# CTENLEDDRVR.net
KiCad netlist of a schematic drawn in Altium Designer
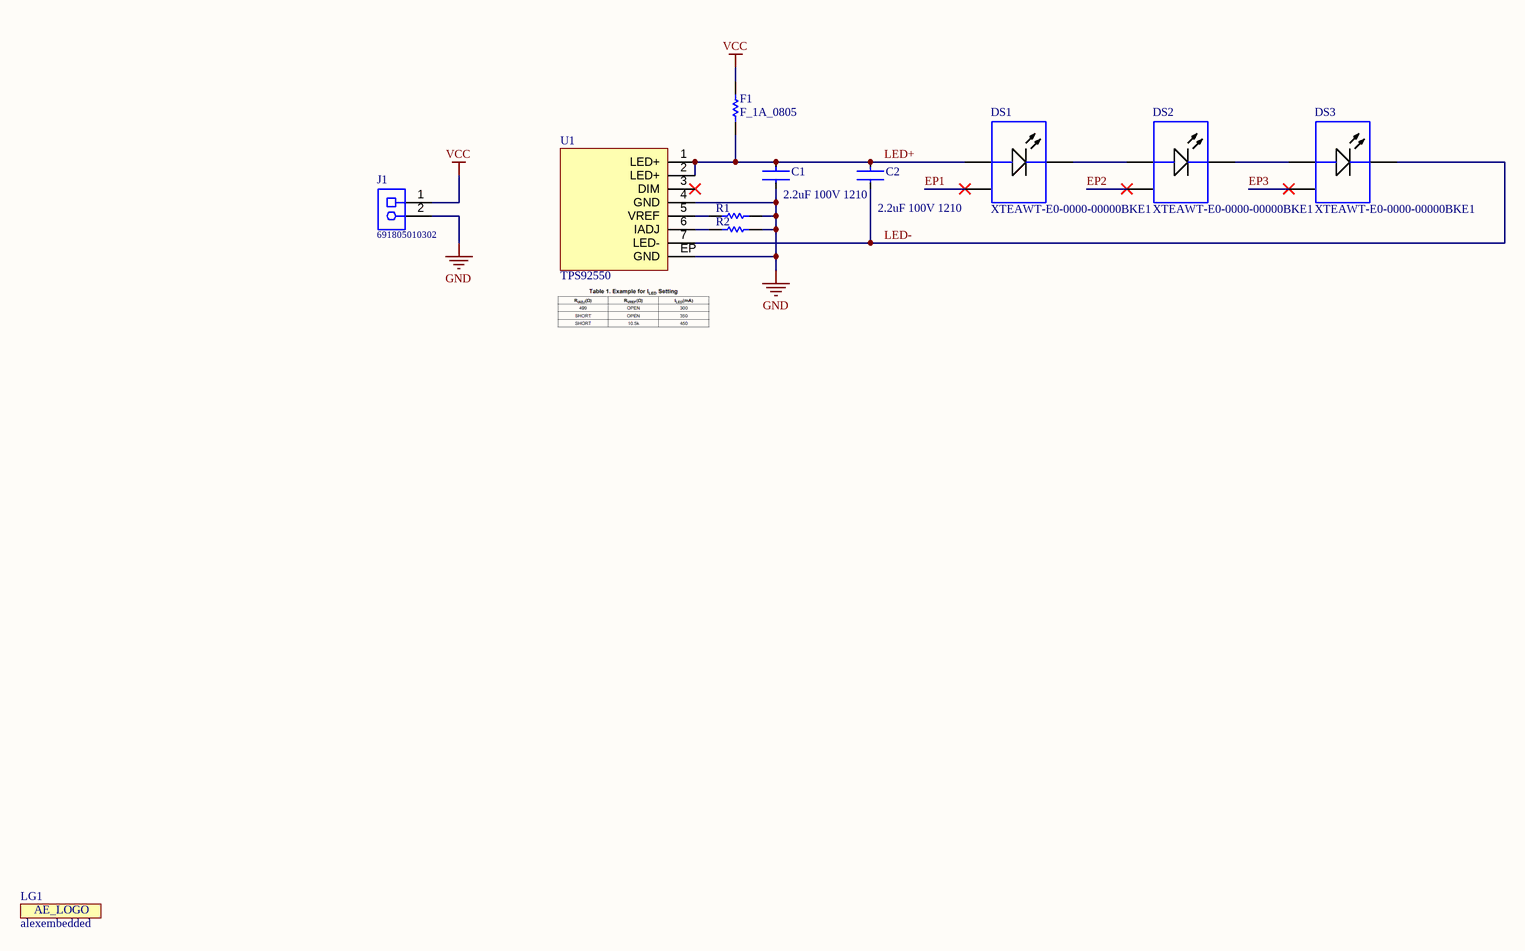
[diagram p0: CTENLEDDRVR.SchDoc]

(export (version "E")
  (design (tool "Eeschema 10.0.6"))
  (components
    (comp (ref "C1")
      (value "2.2uF 100V 1210")
      (footprint "FP-CL32-IPC_C")
      (description "Ceramic capacitor SMD-1210 2200nF (2.2uF) /100V X7R# K +- 10% Samsung, RoHS/2k/")
      (fields (field (name "VOLTAGE") "100V") (field (name "TOLERANCE") "10%"))
      (libsource (lib "Astro Digital US Inc") (part "b4654b650e69147ec39a6b967a45e02"))
    )
    (comp (ref "C2")
      (value "2.2uF 100V 1210")
      (footprint "FP-CL32-IPC_C")
      (description "Ceramic capacitor SMD-1210 2200nF (2.2uF) /100V X7R# K +- 10% Samsung, RoHS/2k/")
      (fields (field (name "VOLTAGE") "100V") (field (name "TOLERANCE") "10%"))
      (libsource (lib "Astro Digital US Inc") (part "b4654b650e69147ec39a6b967a45e02"))
    )
    (comp (ref "DS1")
      (value "XTEAWT-E0-0000-00000BKE1")
      (footprint "CREE-XTE-2_V")
      (description "LED Uni-Color Cool White 6500K 70 2-Pin SMD EP T/R")
      (libsource (lib "Astro Digital US Inc") (part "LED_WHITE-3"))
    )
    (comp (ref "DS2")
      (value "XTEAWT-E0-0000-00000BKE1")
      (footprint "CREE-XTE-2_V")
      (description "LED Uni-Color Cool White 6500K 70 2-Pin SMD EP T/R")
      (libsource (lib "Astro Digital US Inc") (part "LED_WHITE-3"))
    )
    (comp (ref "DS3")
      (value "XTEAWT-E0-0000-00000BKE1")
      (footprint "CREE-XTE-2_V")
      (description "LED Uni-Color Cool White 6500K 70 2-Pin SMD EP T/R")
      (libsource (lib "Astro Digital US Inc") (part "LED_WHITE-3"))
    )
    (comp (ref "F1")
      (value "F_1A_0805")
      (footprint "RESC2013X50X30NL20T20")
      (description "Fuse, 1A, 0805")
      (libsource (lib "Astro Digital US Inc") (part "FUSE"))
    )
    (comp (ref "J1")
      (value "691805010302")
      (footprint "691805010302")
      (description "Serie 8050 - 2.50mm Screwless SMT - WR-TBL, 2 pin")
      (fields (field (name "MANUFACTURER") "Wurth Elektronik") (field (name "PUBLISHER") "WurthElektronik"))
      (libsource (lib "Altium Content Vault") (part "WE-CN-1P-F-R2"))
    )
    (comp (ref "LG1")
      (value "alexembedded")
      (footprint "alexembedded-Footprint-1")
      (description "alexembedded graphic")
      (libsource (lib "Astro Digital US Inc") (part "alexembedded-Symbol-1"))
    )
    (comp (ref "R1")
      (value "R_0R_0603")
      (footprint "RESC1609X50X30LL8T20")
      (description "Res, 0 Ohm, 0603")
      (libsource (lib "Astro Digital US Inc") (part "RES-2"))
    )
    (comp (ref "R2")
      (value "R_0R_0603")
      (footprint "RESC1609X50X30LL8T20")
      (description "Res, 0 Ohm, 0603")
      (libsource (lib "Astro Digital US Inc") (part "RES-2"))
    )
    (comp (ref "U1")
      (value "TPS92550")
      (footprint "TPS92550-Footprint-1")
      (description "LED Driver IC 1 Output DC DC Regulator Step-Down (Buck) PWM Dimming 450mA TO-PMOD-7")
      (libsource (lib "Astro Digital US Inc") (part "TPS92550-Symbol-1"))
    )
  )
  (nets
    (net (code "1") (name "/EP1") (class "Default")
      (node (ref "DS1") (pin "2") (pinfunction "EP_2") (pintype "passive+no_connect"))
    )
    (net (code "2") (name "/EP2") (class "Default")
      (node (ref "DS2") (pin "2") (pinfunction "EP_2") (pintype "passive+no_connect"))
    )
    (net (code "3") (name "/EP3") (class "Default")
      (node (ref "DS3") (pin "2") (pinfunction "EP_2") (pintype "passive+no_connect"))
    )
    (net (code "4") (name "/LED+") (class "Default")
      (node (ref "C1") (pin "1") (pinfunction "1_1") (pintype "passive"))
      (node (ref "C2") (pin "1") (pinfunction "1_1") (pintype "passive"))
      (node (ref "DS1") (pin "1") (pinfunction "A_1") (pintype "passive"))
      (node (ref "F1") (pin "1") (pinfunction "1_1") (pintype "passive"))
      (node (ref "U1") (pin "1") (pinfunction "LED+_1") (pintype "passive"))
      (node (ref "U1") (pin "2") (pinfunction "LED+_2") (pintype "passive"))
    )
    (net (code "5") (name "/LED-") (class "Default")
      (node (ref "C2") (pin "2") (pinfunction "2_2") (pintype "passive"))
      (node (ref "DS3") (pin "3") (pinfunction "K_3") (pintype "passive"))
      (node (ref "U1") (pin "7") (pinfunction "LED-_7") (pintype "passive"))
    )
    (net (code "6") (name "GND") (class "Default")
      (node (ref "C1") (pin "2") (pinfunction "2_2") (pintype "passive"))
      (node (ref "J1") (pin "2") (pinfunction "2_2") (pintype "passive"))
      (node (ref "R1") (pin "2") (pinfunction "2_2") (pintype "passive"))
      (node (ref "R2") (pin "2") (pinfunction "2_2") (pintype "passive"))
      (node (ref "U1") (pin "4") (pinfunction "GND_4") (pintype "passive"))
      (node (ref "U1") (pin "EP") (pinfunction "GND_EP") (pintype "passive"))
    )
    (net (code "7") (name "Net-(DS1-K)") (class "Default")
      (node (ref "DS1") (pin "3") (pinfunction "K_3") (pintype "passive"))
      (node (ref "DS2") (pin "1") (pinfunction "A_1") (pintype "passive"))
    )
    (net (code "8") (name "Net-(DS2-K)") (class "Default")
      (node (ref "DS2") (pin "3") (pinfunction "K_3") (pintype "passive"))
      (node (ref "DS3") (pin "1") (pinfunction "A_1") (pintype "passive"))
    )
    (net (code "9") (name "Net-(U1-IADJ)") (class "Default")
      (node (ref "R2") (pin "1") (pinfunction "1_1") (pintype "passive"))
      (node (ref "U1") (pin "6") (pinfunction "IADJ_6") (pintype "passive"))
    )
    (net (code "10") (name "Net-(U1-VREF)") (class "Default")
      (node (ref "R1") (pin "1") (pinfunction "1_1") (pintype "passive"))
      (node (ref "U1") (pin "5") (pinfunction "VREF_5") (pintype "passive"))
    )
    (net (code "11") (name "VCC") (class "Default")
      (node (ref "F1") (pin "2") (pinfunction "2_2") (pintype "passive"))
      (node (ref "J1") (pin "1") (pinfunction "1_1") (pintype "passive"))
    )
    (net (code "12") (name "unconnected-(U1-DIM-Pad3)") (class "Default")
      (node (ref "U1") (pin "3") (pinfunction "DIM_3") (pintype "passive+no_connect"))
    )
  )
)
